# Mainboard_RMII_Interface.net
KiCad netlist of a schematic drawn in Altium Designer
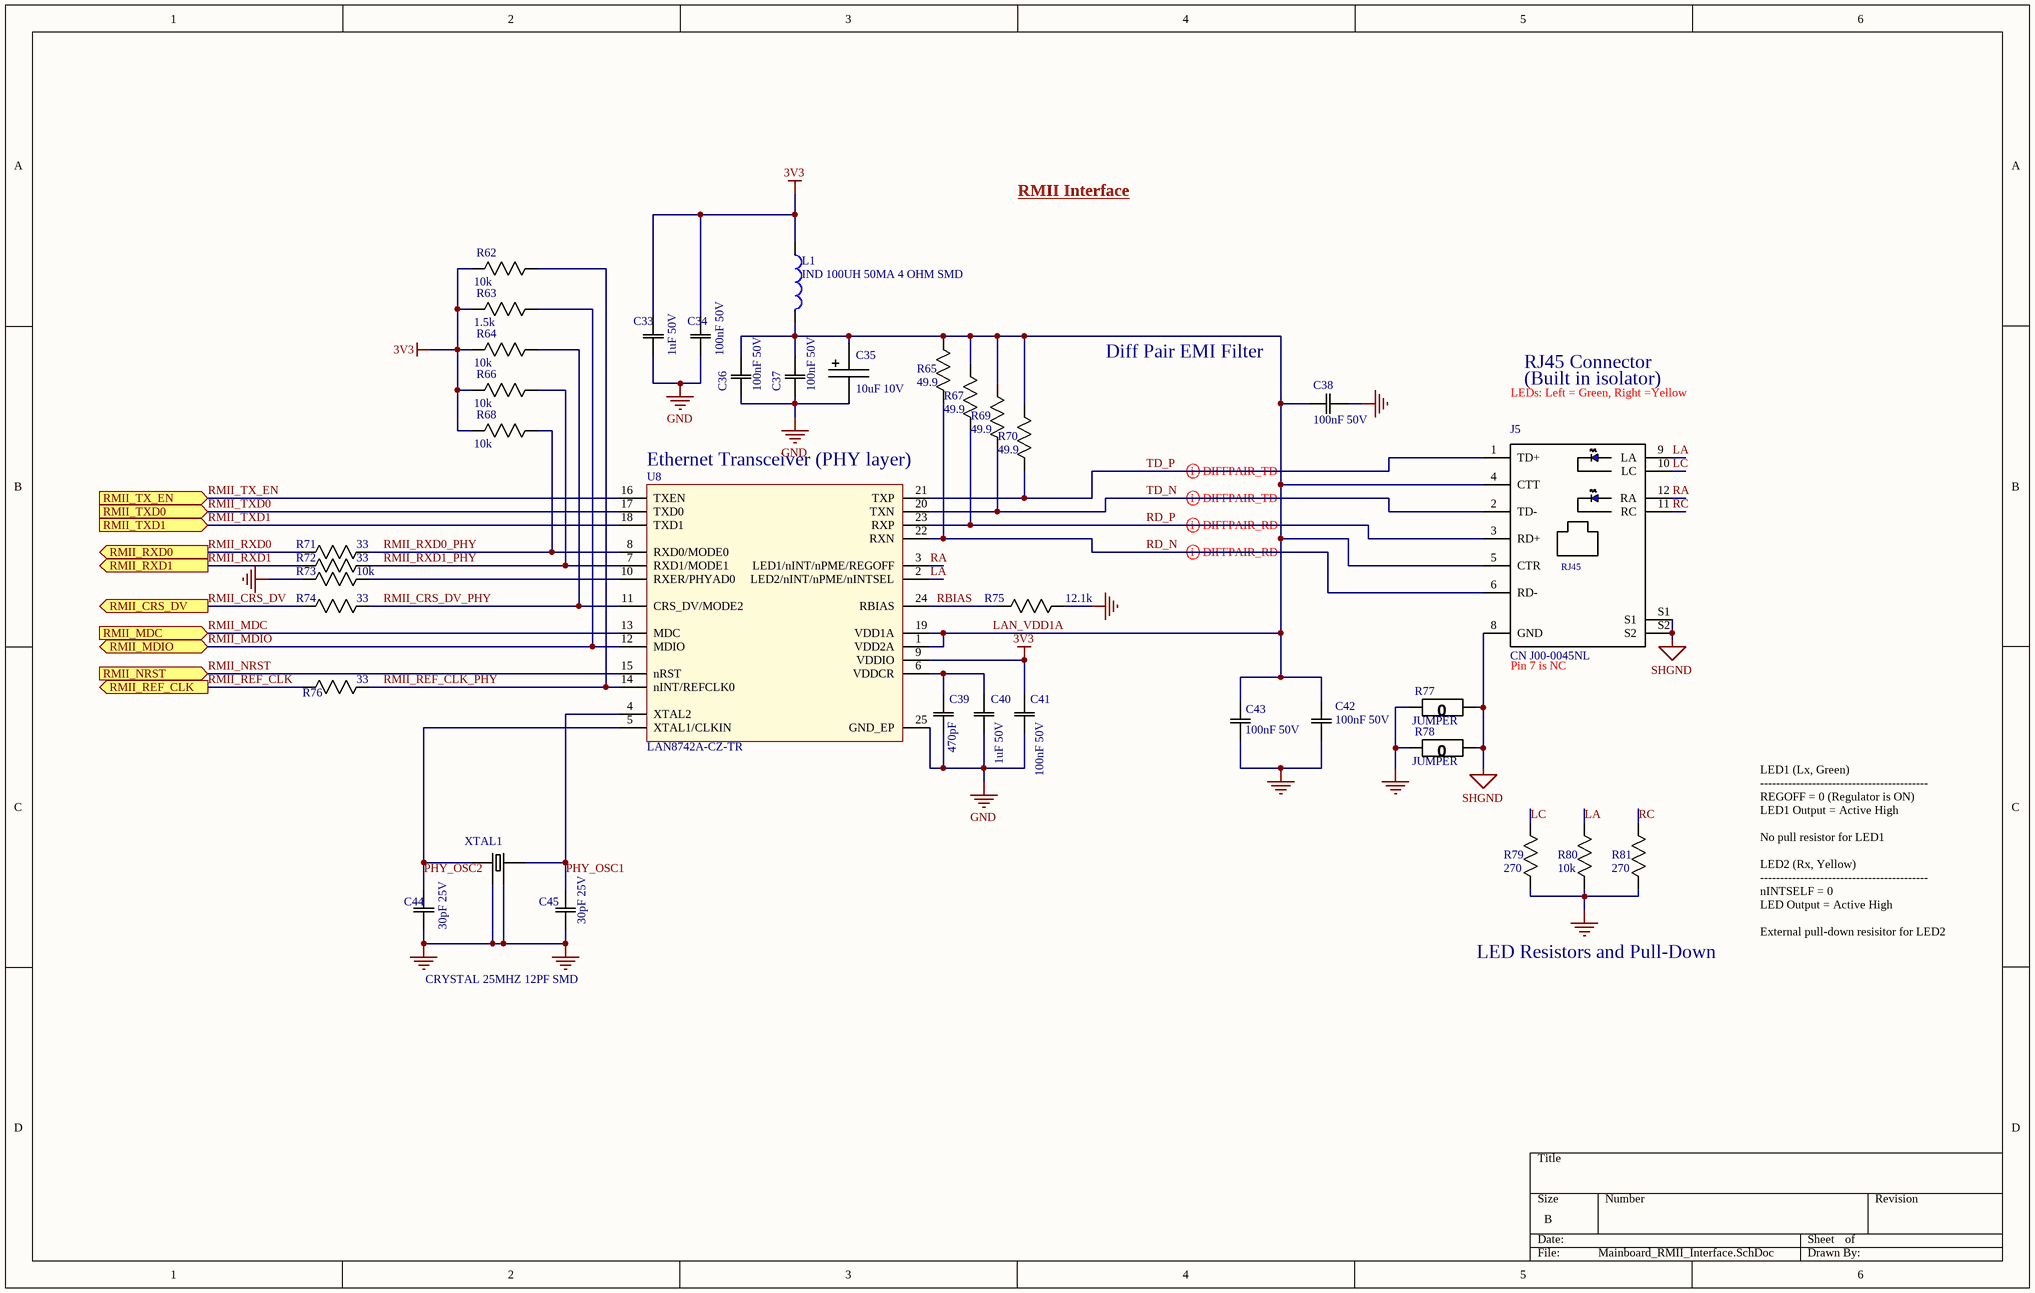
[diagram p0: Mainboard_RMII_Interface.SchDoc]

(export (version "E")
  (design (tool "Eeschema 10.0.6"))
  (components
    (comp (ref "C33")
      (value "1uF 50V")
      (footprint "0603")
      (description "CAP CER 1UF 50V X7R 0805")
      (fields (field (name "TOLERANCE") "10%"))
      (libsource (lib "AltiumLibraries") (part "CAP 1uF 50V"))
    )
    (comp (ref "C34")
      (value "100nF 50V")
      (footprint "0603")
      (description "CAP CER 0.1UF 50V X7R 0805")
      (fields (field (name "TOLERANCE") "10%"))
      (libsource (lib "AltiumLibraries") (part "CAP 100nF 50V"))
    )
    (comp (ref "C35")
      (value "10uF 10V")
      (footprint "1206 Polarized")
      (description "CAP TANT 10UF 10V 1206")
      (fields (field (name "TOLERANCE") "10%"))
      (libsource (lib "AltiumLibraries") (part "CAP TANT 10uF 10V"))
    )
    (comp (ref "C36")
      (value "100nF 50V")
      (footprint "0603")
      (description "CAP CER 0.1UF 50V X7R 0805")
      (fields (field (name "TOLERANCE") "10%"))
      (libsource (lib "AltiumLibraries") (part "CAP 100nF 50V"))
    )
    (comp (ref "C37")
      (value "100nF 50V")
      (footprint "0603")
      (description "CAP CER 0.1UF 50V X7R 0805")
      (fields (field (name "TOLERANCE") "10%"))
      (libsource (lib "AltiumLibraries") (part "CAP 100nF 50V"))
    )
    (comp (ref "C38")
      (value "100nF 50V")
      (footprint "0603")
      (description "CAP CER 0.1UF 50V X7R 0805")
      (fields (field (name "TOLERANCE") "10%"))
      (libsource (lib "AltiumLibraries") (part "CAP 100nF 50V"))
    )
    (comp (ref "C39")
      (value "470pF")
      (footprint "0603")
      (description "CAP CER 470PF 50V X7R 0603/0805")
      (fields (field (name "TOLERANCE") "10%"))
      (libsource (lib "AltiumLibraries") (part "CAP 470pF 50V"))
    )
    (comp (ref "C40")
      (value "1uF 50V")
      (footprint "0603")
      (description "CAP CER 1UF 50V X7R 0805")
      (fields (field (name "TOLERANCE") "10%"))
      (libsource (lib "AltiumLibraries") (part "CAP 1uF 50V"))
    )
    (comp (ref "C41")
      (value "100nF 50V")
      (footprint "0603")
      (description "CAP CER 0.1UF 50V X7R 0805")
      (fields (field (name "TOLERANCE") "10%"))
      (libsource (lib "AltiumLibraries") (part "CAP 100nF 50V"))
    )
    (comp (ref "C42")
      (value "100nF 50V")
      (footprint "0603")
      (description "CAP CER 0.1UF 50V X7R 0805")
      (fields (field (name "TOLERANCE") "10%"))
      (libsource (lib "AltiumLibraries") (part "CAP 100nF 50V"))
    )
    (comp (ref "C43")
      (value "100nF 50V")
      (footprint "0603")
      (description "CAP CER 0.1UF 50V X7R 0805")
      (fields (field (name "TOLERANCE") "10%"))
      (libsource (lib "AltiumLibraries") (part "CAP 100nF 50V"))
    )
    (comp (ref "C44")
      (value "30pF 25V")
      (footprint "0603")
      (description "CAP CER 30PF 25V NP0 0805")
      (fields (field (name "TOLERANCE") "20%"))
      (libsource (lib "AltiumLibraries") (part "CAP 30pF 25V"))
    )
    (comp (ref "C45")
      (value "30pF 25V")
      (footprint "0603")
      (description "CAP CER 30PF 25V NP0 0805")
      (fields (field (name "TOLERANCE") "20%"))
      (libsource (lib "AltiumLibraries") (part "CAP 30pF 25V"))
    )
    (comp (ref "J5")
      (value "CN J00-0045NL")
      (footprint "RJ45 J00-0045NL")
      (description "CN MAGJACK 1PORT 100 BASE-TX")
      (fields (field (name "MF") "Pulse Electronics") (field (name "MP") "J00-0045NL"))
      (libsource (lib "AltiumLibraries") (part "CN MAGJACK"))
    )
    (comp (ref "L1")
      (value "IND 100UH 50MA 4 OHM SMD")
      (footprint "0805")
      (description "100µH Unshielded Wirewound Inductor 50mA 4Ohm 0805 (2012 Metric)")
      (fields (field (name "MF") "Taiyo Yuden") (field (name "MP") "LBR2012T101K"))
      (libsource (lib "AltiumLibraries") (part "IND 100UH 50MA 4 OHM SMD"))
    )
    (comp (ref "R62")
      (value "10k")
      (footprint "0603")
      (description "RES SMD 10K OHM 1% 1/8W 0805")
      (fields (field (name "TOLERANCE") "1%"))
      (libsource (lib "AltiumLibraries") (part "RES 10k 1/8W - 1%"))
    )
    (comp (ref "R63")
      (value "1.5k")
      (footprint "0603")
      (description "RES SMD 1.5K OHM 1% 1/8W 0805")
      (fields (field (name "TOLERANCE") "1%"))
      (libsource (lib "AltiumLibraries") (part "RES 1.5k 1/8W - 1%"))
    )
    (comp (ref "R64")
      (value "10k")
      (footprint "0603")
      (description "RES SMD 10K OHM 1% 1/8W 0805")
      (fields (field (name "TOLERANCE") "1%"))
      (libsource (lib "") (part "RES 10k 1/8W - 1%_1"))
    )
    (comp (ref "R65")
      (value "49.9")
      (footprint "0603")
      (description "RES SMD 49.9 OHM 1% 1/8W 0805")
      (fields (field (name "TOLERANCE") "1%"))
      (libsource (lib "AltiumLibraries") (part "RES 49.9 1/8W"))
    )
    (comp (ref "R66")
      (value "10k")
      (footprint "0603")
      (description "RES SMD 10K OHM 1% 1/8W 0805")
      (fields (field (name "TOLERANCE") "1%"))
      (libsource (lib "AltiumLibraries") (part "RES 10k 1/8W - 1%"))
    )
    (comp (ref "R67")
      (value "49.9")
      (footprint "0603")
      (description "RES SMD 49.9 OHM 1% 1/8W 0805")
      (fields (field (name "TOLERANCE") "1%"))
      (libsource (lib "AltiumLibraries") (part "RES 49.9 1/8W"))
    )
    (comp (ref "R68")
      (value "10k")
      (footprint "0603")
      (description "RES SMD 10K OHM 1% 1/8W 0805")
      (fields (field (name "TOLERANCE") "1%"))
      (libsource (lib "AltiumLibraries") (part "RES 10k 1/8W - 1%"))
    )
    (comp (ref "R69")
      (value "49.9")
      (footprint "0603")
      (description "RES SMD 49.9 OHM 1% 1/8W 0805")
      (fields (field (name "TOLERANCE") "1%"))
      (libsource (lib "AltiumLibraries") (part "RES 49.9 1/8W"))
    )
    (comp (ref "R70")
      (value "49.9")
      (footprint "0603")
      (description "RES SMD 49.9 OHM 1% 1/8W 0805")
      (fields (field (name "TOLERANCE") "1%"))
      (libsource (lib "AltiumLibraries") (part "RES 49.9 1/8W"))
    )
    (comp (ref "R71")
      (value "33")
      (footprint "0603")
      (description "RES SMD 33 OHM 1% 1/8W 0805")
      (fields (field (name "TOLERANCE") "1%"))
      (libsource (lib "AltiumLibraries") (part "RES 33.0 1/8W - 1%"))
    )
    (comp (ref "R72")
      (value "33")
      (footprint "0603")
      (description "RES SMD 33 OHM 1% 1/8W 0805")
      (fields (field (name "TOLERANCE") "1%"))
      (libsource (lib "AltiumLibraries") (part "RES 33.0 1/8W - 1%"))
    )
    (comp (ref "R73")
      (value "10k")
      (footprint "0603")
      (description "RES SMD 10K OHM 1% 1/8W 0805")
      (fields (field (name "TOLERANCE") "1%"))
      (libsource (lib "") (part "RES 10k 1/8W - 1%_1"))
    )
    (comp (ref "R74")
      (value "33")
      (footprint "0603")
      (description "RES SMD 33 OHM 1% 1/8W 0805")
      (fields (field (name "TOLERANCE") "1%"))
      (libsource (lib "AltiumLibraries") (part "RES 33.0 1/8W - 1%"))
    )
    (comp (ref "R75")
      (value "12.1k")
      (footprint "0603")
      (description "RES SMD 12.1K OHM 1% 1/8W 0805")
      (fields (field (name "TOLERANCE") "1%"))
      (libsource (lib "AltiumLibraries") (part "RES 12.1k 1/8W"))
    )
    (comp (ref "R76")
      (value "33")
      (footprint "0603")
      (description "RES SMD 33 OHM 1% 1/8W 0805")
      (fields (field (name "TOLERANCE") "1%"))
      (libsource (lib "AltiumLibraries") (part "RES 33.0 1/8W - 1%"))
    )
    (comp (ref "R77")
      (value "JUMPER")
      (footprint "0603")
      (description "RES SMD 0 OHM JUMPER GENERIC 0805")
      (libsource (lib "AltiumLibraries") (part "RES 0 JUMPER"))
    )
    (comp (ref "R78")
      (value "JUMPER")
      (footprint "0603")
      (description "RES SMD 0 OHM JUMPER GENERIC 0805")
      (libsource (lib "AltiumLibraries") (part "RES 0 JUMPER"))
    )
    (comp (ref "R79")
      (value "270")
      (footprint "0603")
      (description "RES SMD 270 OHM 5% 1/8W 0805")
      (fields (field (name "TOLERANCE") "5%"))
      (libsource (lib "AltiumLibraries") (part "RES 270.0 1/8W"))
    )
    (comp (ref "R80")
      (value "10k")
      (footprint "0603")
      (description "RES SMD 10K OHM 1% 1/8W 0805")
      (fields (field (name "TOLERANCE") "1%"))
      (libsource (lib "AltiumLibraries") (part "RES 10k 1/8W - 1%"))
    )
    (comp (ref "R81")
      (value "270")
      (footprint "0603")
      (description "RES SMD 270 OHM 5% 1/8W 0805")
      (fields (field (name "TOLERANCE") "5%"))
      (libsource (lib "AltiumLibraries") (part "RES 270.0 1/8W"))
    )
    (comp (ref "U8")
      (value "LAN8742A-CZ-TR")
      (footprint "24-QFN (4x4)")
      (fields (field (name "MF") "Microchip Technology"))
      (libsource (lib "AltiumLibraries") (part "LAN8742A-CZ-TR"))
    )
    (comp (ref "XTAL1")
      (value "CRYSTAL 25MHZ 12PF SMD")
      (footprint "3225-4SMD")
      (description "25MHz ±10ppm Crystal 12pF 40 Ohms 2-SMD, No Lead")
      (fields (field (name "MP") "X322525MOB4SI") (field (name "MF") "Yangxing Tech"))
      (libsource (lib "AltiumLibraries") (part "XTAL 25MHZ 12PF SMD4"))
    )
  )
  (nets
    (net (code "1") (name "/LA") (class "Default")
      (node (ref "J5") (pin "9") (pinfunction "LA_9") (pintype "passive"))
      (node (ref "R80") (pin "1") (pinfunction "R1_1") (pintype "passive"))
      (node (ref "U8") (pin "2") (pinfunction "LED2/nINT/nPME/nINTSEL_2") (pintype "passive"))
    )
    (net (code "2") (name "/LAN_VDD1A") (class "Default")
      (node (ref "C35") (pin "1") (pinfunction "P$1_1") (pintype "passive"))
      (node (ref "C36") (pin "2") (pinfunction "C2_2") (pintype "passive"))
      (node (ref "C37") (pin "2") (pinfunction "C2_2") (pintype "passive"))
      (node (ref "C38") (pin "1") (pinfunction "C1_1") (pintype "passive"))
      (node (ref "C42") (pin "2") (pinfunction "C2_2") (pintype "passive"))
      (node (ref "C43") (pin "2") (pinfunction "C2_2") (pintype "passive"))
      (node (ref "J5") (pin "4") (pinfunction "CTT_4") (pintype "passive"))
      (node (ref "J5") (pin "5") (pinfunction "CTR_5") (pintype "passive"))
      (node (ref "L1") (pin "2") (pinfunction "2_2") (pintype "passive"))
      (node (ref "R65") (pin "1") (pinfunction "R1_1") (pintype "passive"))
      (node (ref "R67") (pin "1") (pinfunction "R1_1") (pintype "passive"))
      (node (ref "R69") (pin "1") (pinfunction "R1_1") (pintype "passive"))
      (node (ref "R70") (pin "1") (pinfunction "R1_1") (pintype "passive"))
      (node (ref "U8") (pin "1") (pinfunction "VDD2A_1") (pintype "passive"))
      (node (ref "U8") (pin "19") (pinfunction "VDD1A_19") (pintype "passive"))
    )
    (net (code "3") (name "/LC") (class "Default")
      (node (ref "J5") (pin "10") (pinfunction "LC_10") (pintype "passive"))
      (node (ref "R79") (pin "1") (pinfunction "R1_1") (pintype "passive"))
    )
    (net (code "4") (name "/PHY_OSC1") (class "Default")
      (node (ref "C45") (pin "2") (pinfunction "C2_2") (pintype "passive"))
      (node (ref "U8") (pin "4") (pinfunction "XTAL2_4") (pintype "passive"))
      (node (ref "XTAL1") (pin "3") (pinfunction "3_3") (pintype "passive"))
    )
    (net (code "5") (name "/PHY_OSC2") (class "Default")
      (node (ref "C44") (pin "2") (pinfunction "C2_2") (pintype "passive"))
      (node (ref "U8") (pin "5") (pinfunction "XTAL1/CLKIN_5") (pintype "passive"))
      (node (ref "XTAL1") (pin "1") (pinfunction "1_1") (pintype "passive"))
    )
    (net (code "6") (name "/RA") (class "Default")
      (node (ref "J5") (pin "12") (pinfunction "RA_12") (pintype "passive"))
      (node (ref "U8") (pin "3") (pinfunction "LED1/nINT/nPME/REGOFF_3") (pintype "passive"))
    )
    (net (code "7") (name "/RBIAS") (class "Default")
      (node (ref "R75") (pin "2") (pinfunction "R2_2") (pintype "passive"))
      (node (ref "U8") (pin "24") (pinfunction "RBIAS_24") (pintype "passive"))
    )
    (net (code "8") (name "/RC") (class "Default")
      (node (ref "J5") (pin "11") (pinfunction "RC_11") (pintype "passive"))
      (node (ref "R81") (pin "1") (pinfunction "R1_1") (pintype "passive"))
    )
    (net (code "9") (name "/RD_N") (class "Default")
      (node (ref "J5") (pin "6") (pinfunction "RD-_6") (pintype "passive"))
      (node (ref "R65") (pin "2") (pinfunction "R2_2") (pintype "passive"))
      (node (ref "U8") (pin "22") (pinfunction "RXN_22") (pintype "passive"))
    )
    (net (code "10") (name "/RD_P") (class "Default")
      (node (ref "J5") (pin "3") (pinfunction "RD+_3") (pintype "passive"))
      (node (ref "R67") (pin "2") (pinfunction "R2_2") (pintype "passive"))
      (node (ref "U8") (pin "23") (pinfunction "RXP_23") (pintype "passive"))
    )
    (net (code "11") (name "/RMII_CRS_DV") (class "Default")
      (node (ref "R74") (pin "2") (pinfunction "R2_2") (pintype "passive"))
    )
    (net (code "12") (name "/RMII_CRS_DV_PHY") (class "Default")
      (node (ref "R64") (pin "1") (pinfunction "R1_1") (pintype "passive"))
      (node (ref "R74") (pin "1") (pinfunction "R1_1") (pintype "passive"))
      (node (ref "U8") (pin "11") (pinfunction "CRS_DV/MODE2_11") (pintype "passive"))
    )
    (net (code "13") (name "/RMII_MDC") (class "Default")
      (node (ref "U8") (pin "13") (pinfunction "MDC_13") (pintype "passive"))
    )
    (net (code "14") (name "/RMII_MDIO") (class "Default")
      (node (ref "R63") (pin "1") (pinfunction "R1_1") (pintype "passive"))
      (node (ref "U8") (pin "12") (pinfunction "MDIO_12") (pintype "passive"))
    )
    (net (code "15") (name "/RMII_NRST") (class "Default")
      (node (ref "U8") (pin "15") (pinfunction "nRST_15") (pintype "passive"))
    )
    (net (code "16") (name "/RMII_REF_CLK") (class "Default")
      (node (ref "R76") (pin "2") (pinfunction "R2_2") (pintype "passive"))
    )
    (net (code "17") (name "/RMII_REF_CLK_PHY") (class "Default")
      (node (ref "R62") (pin "1") (pinfunction "R1_1") (pintype "passive"))
      (node (ref "R76") (pin "1") (pinfunction "R1_1") (pintype "passive"))
      (node (ref "U8") (pin "14") (pinfunction "nINT/REFCLK0_14") (pintype "passive"))
    )
    (net (code "18") (name "/RMII_RXD0") (class "Default")
      (node (ref "R71") (pin "2") (pinfunction "R2_2") (pintype "passive"))
    )
    (net (code "19") (name "/RMII_RXD0_PHY") (class "Default")
      (node (ref "R68") (pin "1") (pinfunction "R1_1") (pintype "passive"))
      (node (ref "R71") (pin "1") (pinfunction "R1_1") (pintype "passive"))
      (node (ref "U8") (pin "8") (pinfunction "RXD0/MODE0_8") (pintype "passive"))
    )
    (net (code "20") (name "/RMII_RXD1") (class "Default")
      (node (ref "R72") (pin "2") (pinfunction "R2_2") (pintype "passive"))
    )
    (net (code "21") (name "/RMII_RXD1_PHY") (class "Default")
      (node (ref "R66") (pin "1") (pinfunction "R1_1") (pintype "passive"))
      (node (ref "R72") (pin "1") (pinfunction "R1_1") (pintype "passive"))
      (node (ref "U8") (pin "7") (pinfunction "RXD1/MODE1_7") (pintype "passive"))
    )
    (net (code "22") (name "/RMII_TXD0") (class "Default")
      (node (ref "U8") (pin "17") (pinfunction "TXD0_17") (pintype "passive"))
    )
    (net (code "23") (name "/RMII_TXD1") (class "Default")
      (node (ref "U8") (pin "18") (pinfunction "TXD1_18") (pintype "passive"))
    )
    (net (code "24") (name "/RMII_TX_EN") (class "Default")
      (node (ref "U8") (pin "16") (pinfunction "TXEN_16") (pintype "passive"))
    )
    (net (code "25") (name "/TD_N") (class "Default")
      (node (ref "J5") (pin "2") (pinfunction "TD-_2") (pintype "passive"))
      (node (ref "R69") (pin "2") (pinfunction "R2_2") (pintype "passive"))
      (node (ref "U8") (pin "20") (pinfunction "TXN_20") (pintype "passive"))
    )
    (net (code "26") (name "/TD_P") (class "Default")
      (node (ref "J5") (pin "1") (pinfunction "TD+_1") (pintype "passive"))
      (node (ref "R70") (pin "2") (pinfunction "R2_2") (pintype "passive"))
      (node (ref "U8") (pin "21") (pinfunction "TXP_21") (pintype "passive"))
    )
    (net (code "27") (name "3V3") (class "Default")
      (node (ref "C33") (pin "2") (pinfunction "C2_2") (pintype "passive"))
      (node (ref "C34") (pin "2") (pinfunction "C2_2") (pintype "passive"))
      (node (ref "C41") (pin "2") (pinfunction "C2_2") (pintype "passive"))
      (node (ref "L1") (pin "1") (pinfunction "1_1") (pintype "passive"))
      (node (ref "R62") (pin "2") (pinfunction "R2_2") (pintype "passive"))
      (node (ref "R63") (pin "2") (pinfunction "R2_2") (pintype "passive"))
      (node (ref "R64") (pin "2") (pinfunction "R2_2") (pintype "passive"))
      (node (ref "R66") (pin "2") (pinfunction "R2_2") (pintype "passive"))
      (node (ref "R68") (pin "2") (pinfunction "R2_2") (pintype "passive"))
      (node (ref "U8") (pin "9") (pinfunction "VDDIO_9") (pintype "passive"))
    )
    (net (code "28") (name "GND") (class "Default")
      (node (ref "C33") (pin "1") (pinfunction "C1_1") (pintype "passive"))
      (node (ref "C34") (pin "1") (pinfunction "C1_1") (pintype "passive"))
      (node (ref "C35") (pin "2") (pinfunction "P$2_2") (pintype "passive"))
      (node (ref "C36") (pin "1") (pinfunction "C1_1") (pintype "passive"))
      (node (ref "C37") (pin "1") (pinfunction "C1_1") (pintype "passive"))
      (node (ref "C38") (pin "2") (pinfunction "C2_2") (pintype "passive"))
      (node (ref "C39") (pin "1") (pinfunction "C1_1") (pintype "passive"))
      (node (ref "C40") (pin "1") (pinfunction "C1_1") (pintype "passive"))
      (node (ref "C41") (pin "1") (pinfunction "C1_1") (pintype "passive"))
      (node (ref "C42") (pin "1") (pinfunction "C1_1") (pintype "passive"))
      (node (ref "C43") (pin "1") (pinfunction "C1_1") (pintype "passive"))
      (node (ref "C44") (pin "1") (pinfunction "C1_1") (pintype "passive"))
      (node (ref "C45") (pin "1") (pinfunction "C1_1") (pintype "passive"))
      (node (ref "R73") (pin "2") (pinfunction "R2_2") (pintype "passive"))
      (node (ref "R75") (pin "1") (pinfunction "R1_1") (pintype "passive"))
      (node (ref "R77") (pin "2") (pinfunction "R2_2") (pintype "passive"))
      (node (ref "R78") (pin "2") (pinfunction "R2_2") (pintype "passive"))
      (node (ref "R79") (pin "2") (pinfunction "R2_2") (pintype "passive"))
      (node (ref "R80") (pin "2") (pinfunction "R2_2") (pintype "passive"))
      (node (ref "R81") (pin "2") (pinfunction "R2_2") (pintype "passive"))
      (node (ref "U8") (pin "25") (pinfunction "GND_EP_25") (pintype "passive"))
      (node (ref "XTAL1") (pin "2") (pinfunction "2_2") (pintype "passive"))
      (node (ref "XTAL1") (pin "4") (pinfunction "4_4") (pintype "passive"))
    )
    (net (code "29") (name "Net-(C39-C2)") (class "Default")
      (node (ref "C39") (pin "2") (pinfunction "C2_2") (pintype "passive"))
      (node (ref "C40") (pin "2") (pinfunction "C2_2") (pintype "passive"))
      (node (ref "U8") (pin "6") (pinfunction "VDDCR_6") (pintype "passive"))
    )
    (net (code "30") (name "Net-(R73-R1)") (class "Default")
      (node (ref "R73") (pin "1") (pinfunction "R1_1") (pintype "passive"))
      (node (ref "U8") (pin "10") (pinfunction "RXER/PHYAD0_10") (pintype "passive"))
    )
    (net (code "31") (name "SHGND") (class "Default")
      (node (ref "J5") (pin "8") (pinfunction "GND_8") (pintype "passive"))
      (node (ref "J5") (pin "S1") (pinfunction "S1_S1") (pintype "passive"))
      (node (ref "J5") (pin "S2") (pinfunction "S2_S2") (pintype "passive"))
      (node (ref "R77") (pin "1") (pinfunction "R1_1") (pintype "passive"))
      (node (ref "R78") (pin "1") (pinfunction "R1_1") (pintype "passive"))
    )
  )
)
